# PCB-BI8-2x4_PCBAtest.net
KiCad netlist of a schematic drawn in EAGLE
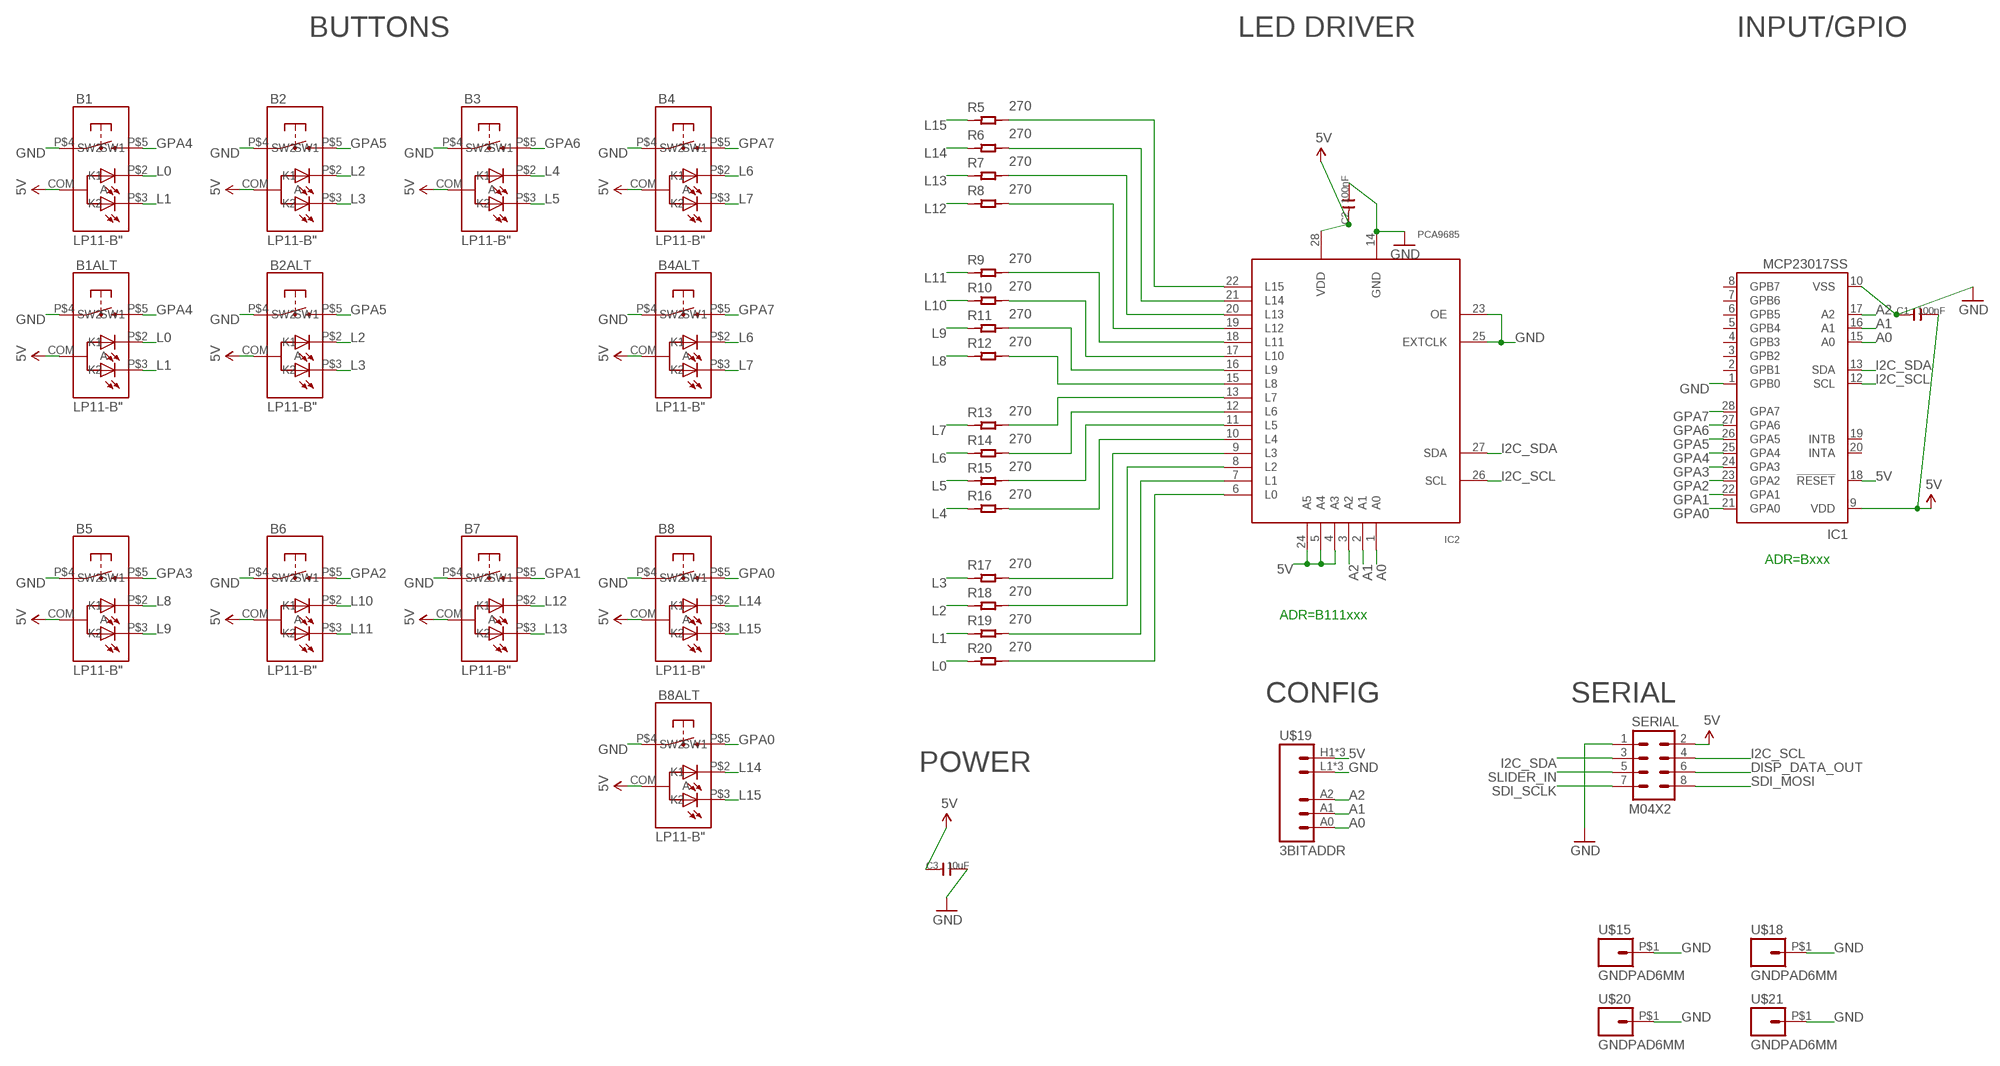
[diagram p0: schematic, sheet 1]

(export (version "E")
  (design (tool "Eeschema 10.0.6"))
  (components
    (comp (ref "B1")
      (value "LP11-B\"")
      (footprint "eagle-import:LP11")
      (libsource (lib "eagle-import") (part "LP11-B{dblquote}"))
    )
    (comp (ref "B1ALT")
      (value "LP11-B\"")
      (footprint "eagle-import:LP11")
      (libsource (lib "eagle-import") (part "LP11-B{dblquote}"))
    )
    (comp (ref "B2")
      (value "LP11-B\"")
      (footprint "eagle-import:LP11")
      (libsource (lib "eagle-import") (part "LP11-B{dblquote}"))
    )
    (comp (ref "B2ALT")
      (value "LP11-B\"")
      (footprint "eagle-import:LP11")
      (libsource (lib "eagle-import") (part "LP11-B{dblquote}"))
    )
    (comp (ref "B3")
      (value "LP11-B\"")
      (footprint "eagle-import:LP11")
      (libsource (lib "eagle-import") (part "LP11-B{dblquote}"))
    )
    (comp (ref "B4")
      (value "LP11-B\"")
      (footprint "eagle-import:LP11")
      (libsource (lib "eagle-import") (part "LP11-B{dblquote}"))
    )
    (comp (ref "B4ALT")
      (value "LP11-B\"")
      (footprint "eagle-import:LP11")
      (libsource (lib "eagle-import") (part "LP11-B{dblquote}"))
    )
    (comp (ref "B5")
      (value "LP11-B\"")
      (footprint "eagle-import:LP11")
      (libsource (lib "eagle-import") (part "LP11-B{dblquote}"))
    )
    (comp (ref "B6")
      (value "LP11-B\"")
      (footprint "eagle-import:LP11")
      (libsource (lib "eagle-import") (part "LP11-B{dblquote}"))
    )
    (comp (ref "B7")
      (value "LP11-B\"")
      (footprint "eagle-import:LP11")
      (libsource (lib "eagle-import") (part "LP11-B{dblquote}"))
    )
    (comp (ref "B8")
      (value "LP11-B\"")
      (footprint "eagle-import:LP11")
      (libsource (lib "eagle-import") (part "LP11-B{dblquote}"))
    )
    (comp (ref "B8ALT")
      (value "LP11-B\"")
      (footprint "eagle-import:LP11")
      (libsource (lib "eagle-import") (part "LP11-B{dblquote}"))
    )
    (comp (ref "C1")
      (value "100nF")
      (footprint "eagle-import:C0603")
      (libsource (lib "eagle-import") (part "C-0603"))
    )
    (comp (ref "C2")
      (value "100nF")
      (footprint "eagle-import:C0603")
      (libsource (lib "eagle-import") (part "C-0603"))
    )
    (comp (ref "C3")
      (value "10uF")
      (footprint "eagle-import:C0805")
      (libsource (lib "eagle-import") (part "C-0805"))
    )
    (comp (ref "IC1")
      (value "MCP23017SS")
      (footprint "eagle-import:SSOP28")
      (fields
        (field (name "MF") "MICROCHIP")
        (field (name "MPN") "MCP23017-E/SS")
        (field (name "MPN_1") "MCP23017-E/SS")
        (field (name "OC_FARNELL") "1467674")
        (field (name "OC_NEWARK") "31K2960")
      )
      (libsource (lib "eagle-import") (part "MCP23017SS"))
    )
    (comp (ref "IC2")
      (value "PCA9685")
      (footprint "eagle-import:TSSOP28")
      (libsource (lib "eagle-import") (part "PCA9685"))
    )
    (comp (ref "R5")
      (value "270")
      (footprint "eagle-import:R0603")
      (libsource (lib "eagle-import") (part "R-0603"))
    )
    (comp (ref "R6")
      (value "270")
      (footprint "eagle-import:R0603")
      (libsource (lib "eagle-import") (part "R-0603"))
    )
    (comp (ref "R7")
      (value "270")
      (footprint "eagle-import:R0603")
      (libsource (lib "eagle-import") (part "R-0603"))
    )
    (comp (ref "R8")
      (value "270")
      (footprint "eagle-import:R0603")
      (libsource (lib "eagle-import") (part "R-0603"))
    )
    (comp (ref "R9")
      (value "270")
      (footprint "eagle-import:R0603")
      (libsource (lib "eagle-import") (part "R-0603"))
    )
    (comp (ref "R10")
      (value "270")
      (footprint "eagle-import:R0603")
      (libsource (lib "eagle-import") (part "R-0603"))
    )
    (comp (ref "R11")
      (value "270")
      (footprint "eagle-import:R0603")
      (libsource (lib "eagle-import") (part "R-0603"))
    )
    (comp (ref "R12")
      (value "270")
      (footprint "eagle-import:R0603")
      (libsource (lib "eagle-import") (part "R-0603"))
    )
    (comp (ref "R13")
      (value "270")
      (footprint "eagle-import:R0603")
      (libsource (lib "eagle-import") (part "R-0603"))
    )
    (comp (ref "R14")
      (value "270")
      (footprint "eagle-import:R0603")
      (libsource (lib "eagle-import") (part "R-0603"))
    )
    (comp (ref "R15")
      (value "270")
      (footprint "eagle-import:R0603")
      (libsource (lib "eagle-import") (part "R-0603"))
    )
    (comp (ref "R16")
      (value "270")
      (footprint "eagle-import:R0603")
      (libsource (lib "eagle-import") (part "R-0603"))
    )
    (comp (ref "R17")
      (value "270")
      (footprint "eagle-import:R0603")
      (libsource (lib "eagle-import") (part "R-0603"))
    )
    (comp (ref "R18")
      (value "270")
      (footprint "eagle-import:R0603")
      (libsource (lib "eagle-import") (part "R-0603"))
    )
    (comp (ref "R19")
      (value "270")
      (footprint "eagle-import:R0603")
      (libsource (lib "eagle-import") (part "R-0603"))
    )
    (comp (ref "R20")
      (value "270")
      (footprint "eagle-import:R0603")
      (libsource (lib "eagle-import") (part "R-0603"))
    )
    (comp (ref "SERIAL")
      (value "M04X2")
      (footprint "eagle-import:2X4")
      (libsource (lib "eagle-import") (part "M04X2"))
    )
    (comp (ref "U$15")
      (value "GNDPAD6MM")
      (footprint "eagle-import:3.2MMPAD6MM")
      (libsource (lib "eagle-import") (part "GNDPAD6MM"))
    )
    (comp (ref "U$18")
      (value "GNDPAD6MM")
      (footprint "eagle-import:3.2MMPAD6MM")
      (libsource (lib "eagle-import") (part "GNDPAD6MM"))
    )
    (comp (ref "U$19")
      (value "3BITADDR")
      (footprint "eagle-import:3BITADDR")
      (libsource (lib "eagle-import") (part "3BITADDR"))
    )
    (comp (ref "U$20")
      (value "GNDPAD6MM")
      (footprint "eagle-import:3.2MMPAD6MM")
      (libsource (lib "eagle-import") (part "GNDPAD6MM"))
    )
    (comp (ref "U$21")
      (value "GNDPAD6MM")
      (footprint "eagle-import:3.2MMPAD6MM")
      (libsource (lib "eagle-import") (part "GNDPAD6MM"))
    )
  )
  (nets
    (net (code "1") (name "5V") (class "Default")
      (node (ref "B1") (pin "COM") (pinfunction "A_COM") (pintype "bidirectional"))
      (node (ref "B1ALT") (pin "COM") (pinfunction "A_COM") (pintype "bidirectional"))
      (node (ref "B2") (pin "COM") (pinfunction "A_COM") (pintype "bidirectional"))
      (node (ref "B2ALT") (pin "COM") (pinfunction "A_COM") (pintype "bidirectional"))
      (node (ref "B3") (pin "COM") (pinfunction "A_COM") (pintype "bidirectional"))
      (node (ref "B4") (pin "COM") (pinfunction "A_COM") (pintype "bidirectional"))
      (node (ref "B4ALT") (pin "COM") (pinfunction "A_COM") (pintype "bidirectional"))
      (node (ref "B5") (pin "COM") (pinfunction "A_COM") (pintype "bidirectional"))
      (node (ref "B6") (pin "COM") (pinfunction "A_COM") (pintype "bidirectional"))
      (node (ref "B7") (pin "COM") (pinfunction "A_COM") (pintype "bidirectional"))
      (node (ref "B8") (pin "COM") (pinfunction "A_COM") (pintype "bidirectional"))
      (node (ref "B8ALT") (pin "COM") (pinfunction "A_COM") (pintype "bidirectional"))
      (node (ref "C1") (pin "2") (pinfunction "2_2") (pintype "bidirectional"))
      (node (ref "C2") (pin "1") (pinfunction "1_1") (pintype "bidirectional"))
      (node (ref "C3") (pin "1") (pinfunction "1_1") (pintype "bidirectional"))
      (node (ref "IC1") (pin "18") (pinfunction "~{RESET}_18") (pintype "input"))
      (node (ref "IC1") (pin "9") (pinfunction "VDD_9") (pintype "power_in"))
      (node (ref "IC2") (pin "24") (pinfunction "A5_24") (pintype "input"))
      (node (ref "IC2") (pin "28") (pinfunction "VDD_28") (pintype "power_in"))
      (node (ref "IC2") (pin "4") (pinfunction "A3_4") (pintype "input"))
      (node (ref "IC2") (pin "5") (pinfunction "A4_5") (pintype "input"))
      (node (ref "SERIAL") (pin "2") (pinfunction "2_2") (pintype "passive"))
      (node (ref "U$19") (pin "H1") (pinfunction "VCC_H1") (pintype "passive"))
      (node (ref "U$19") (pin "H2") (pinfunction "VCC_H2") (pintype "passive"))
      (node (ref "U$19") (pin "H3") (pinfunction "VCC_H3") (pintype "passive"))
    )
    (net (code "2") (name "A0") (class "Default")
      (node (ref "IC1") (pin "15") (pinfunction "A0_15") (pintype "input"))
      (node (ref "IC2") (pin "1") (pinfunction "A0_1") (pintype "input"))
      (node (ref "U$19") (pin "A0") (pinfunction "A0_A0") (pintype "passive"))
    )
    (net (code "3") (name "A1") (class "Default")
      (node (ref "IC1") (pin "16") (pinfunction "A1_16") (pintype "input"))
      (node (ref "IC2") (pin "2") (pinfunction "A1_2") (pintype "input"))
      (node (ref "U$19") (pin "A1") (pinfunction "A1_A1") (pintype "passive"))
    )
    (net (code "4") (name "A2") (class "Default")
      (node (ref "IC1") (pin "17") (pinfunction "A2_17") (pintype "input"))
      (node (ref "IC2") (pin "3") (pinfunction "A2_3") (pintype "input"))
      (node (ref "U$19") (pin "A2") (pinfunction "A2_A2") (pintype "passive"))
    )
    (net (code "5") (name "DISP_DATA_OUT") (class "Default")
      (node (ref "SERIAL") (pin "6") (pinfunction "6_6") (pintype "passive"))
    )
    (net (code "6") (name "GND") (class "Default")
      (node (ref "B1") (pin "P$4") (pinfunction "SW1_P$4") (pintype "bidirectional"))
      (node (ref "B1ALT") (pin "P$4") (pinfunction "SW1_P$4") (pintype "bidirectional"))
      (node (ref "B2") (pin "P$4") (pinfunction "SW1_P$4") (pintype "bidirectional"))
      (node (ref "B2ALT") (pin "P$4") (pinfunction "SW1_P$4") (pintype "bidirectional"))
      (node (ref "B3") (pin "P$4") (pinfunction "SW1_P$4") (pintype "bidirectional"))
      (node (ref "B4") (pin "P$4") (pinfunction "SW1_P$4") (pintype "bidirectional"))
      (node (ref "B4ALT") (pin "P$4") (pinfunction "SW1_P$4") (pintype "bidirectional"))
      (node (ref "B5") (pin "P$4") (pinfunction "SW1_P$4") (pintype "bidirectional"))
      (node (ref "B6") (pin "P$4") (pinfunction "SW1_P$4") (pintype "bidirectional"))
      (node (ref "B7") (pin "P$4") (pinfunction "SW1_P$4") (pintype "bidirectional"))
      (node (ref "B8") (pin "P$4") (pinfunction "SW1_P$4") (pintype "bidirectional"))
      (node (ref "B8ALT") (pin "P$4") (pinfunction "SW1_P$4") (pintype "bidirectional"))
      (node (ref "C1") (pin "1") (pinfunction "1_1") (pintype "bidirectional"))
      (node (ref "C2") (pin "2") (pinfunction "2_2") (pintype "bidirectional"))
      (node (ref "C3") (pin "2") (pinfunction "2_2") (pintype "bidirectional"))
      (node (ref "IC1") (pin "1") (pinfunction "GPB0_1") (pintype "bidirectional"))
      (node (ref "IC1") (pin "10") (pinfunction "VSS_10") (pintype "power_in"))
      (node (ref "IC2") (pin "14") (pinfunction "GND_14") (pintype "power_in"))
      (node (ref "IC2") (pin "23") (pinfunction "OE_23") (pintype "input"))
      (node (ref "IC2") (pin "25") (pinfunction "EXTCLK_25") (pintype "input"))
      (node (ref "SERIAL") (pin "1") (pinfunction "1_1") (pintype "passive"))
      (node (ref "U$15") (pin "P$1") (pinfunction "1_P$1") (pintype "passive"))
      (node (ref "U$18") (pin "P$1") (pinfunction "1_P$1") (pintype "passive"))
      (node (ref "U$19") (pin "L1") (pinfunction "GND_L1") (pintype "passive"))
      (node (ref "U$19") (pin "L2") (pinfunction "GND_L2") (pintype "passive"))
      (node (ref "U$19") (pin "L3") (pinfunction "GND_L3") (pintype "passive"))
      (node (ref "U$20") (pin "P$1") (pinfunction "1_P$1") (pintype "passive"))
      (node (ref "U$21") (pin "P$1") (pinfunction "1_P$1") (pintype "passive"))
    )
    (net (code "7") (name "GPA0") (class "Default")
      (node (ref "B8") (pin "P$5") (pinfunction "SW2_P$5") (pintype "bidirectional"))
      (node (ref "B8ALT") (pin "P$5") (pinfunction "SW2_P$5") (pintype "bidirectional"))
      (node (ref "IC1") (pin "21") (pinfunction "GPA0_21") (pintype "bidirectional"))
    )
    (net (code "8") (name "GPA1") (class "Default")
      (node (ref "B7") (pin "P$5") (pinfunction "SW2_P$5") (pintype "bidirectional"))
      (node (ref "IC1") (pin "22") (pinfunction "GPA1_22") (pintype "bidirectional"))
    )
    (net (code "9") (name "GPA2") (class "Default")
      (node (ref "B6") (pin "P$5") (pinfunction "SW2_P$5") (pintype "bidirectional"))
      (node (ref "IC1") (pin "23") (pinfunction "GPA2_23") (pintype "bidirectional"))
    )
    (net (code "10") (name "GPA3") (class "Default")
      (node (ref "B5") (pin "P$5") (pinfunction "SW2_P$5") (pintype "bidirectional"))
      (node (ref "IC1") (pin "24") (pinfunction "GPA3_24") (pintype "bidirectional"))
    )
    (net (code "11") (name "GPA4") (class "Default")
      (node (ref "B1") (pin "P$5") (pinfunction "SW2_P$5") (pintype "bidirectional"))
      (node (ref "B1ALT") (pin "P$5") (pinfunction "SW2_P$5") (pintype "bidirectional"))
      (node (ref "IC1") (pin "25") (pinfunction "GPA4_25") (pintype "bidirectional"))
    )
    (net (code "12") (name "GPA5") (class "Default")
      (node (ref "B2") (pin "P$5") (pinfunction "SW2_P$5") (pintype "bidirectional"))
      (node (ref "B2ALT") (pin "P$5") (pinfunction "SW2_P$5") (pintype "bidirectional"))
      (node (ref "IC1") (pin "26") (pinfunction "GPA5_26") (pintype "bidirectional"))
    )
    (net (code "13") (name "GPA6") (class "Default")
      (node (ref "B3") (pin "P$5") (pinfunction "SW2_P$5") (pintype "bidirectional"))
      (node (ref "IC1") (pin "27") (pinfunction "GPA6_27") (pintype "bidirectional"))
    )
    (net (code "14") (name "GPA7") (class "Default")
      (node (ref "B4") (pin "P$5") (pinfunction "SW2_P$5") (pintype "bidirectional"))
      (node (ref "B4ALT") (pin "P$5") (pinfunction "SW2_P$5") (pintype "bidirectional"))
      (node (ref "IC1") (pin "28") (pinfunction "GPA7_28") (pintype "bidirectional"))
    )
    (net (code "15") (name "I2C_SCL") (class "Default")
      (node (ref "IC1") (pin "12") (pinfunction "SCL_12") (pintype "input"))
      (node (ref "IC2") (pin "26") (pinfunction "SCL_26") (pintype "input"))
      (node (ref "SERIAL") (pin "4") (pinfunction "4_4") (pintype "passive"))
    )
    (net (code "16") (name "I2C_SDA") (class "Default")
      (node (ref "IC1") (pin "13") (pinfunction "SDA_13") (pintype "bidirectional"))
      (node (ref "IC2") (pin "27") (pinfunction "SDA_27") (pintype "input"))
      (node (ref "SERIAL") (pin "3") (pinfunction "3_3") (pintype "passive"))
    )
    (net (code "17") (name "L0") (class "Default")
      (node (ref "B1") (pin "P$2") (pinfunction "K1_P$2") (pintype "bidirectional"))
      (node (ref "B1ALT") (pin "P$2") (pinfunction "K1_P$2") (pintype "bidirectional"))
      (node (ref "R20") (pin "1") (pinfunction "1_1") (pintype "bidirectional"))
    )
    (net (code "18") (name "L1") (class "Default")
      (node (ref "B1") (pin "P$3") (pinfunction "K2_P$3") (pintype "bidirectional"))
      (node (ref "B1ALT") (pin "P$3") (pinfunction "K2_P$3") (pintype "bidirectional"))
      (node (ref "R19") (pin "1") (pinfunction "1_1") (pintype "bidirectional"))
    )
    (net (code "19") (name "L2") (class "Default")
      (node (ref "B2") (pin "P$2") (pinfunction "K1_P$2") (pintype "bidirectional"))
      (node (ref "B2ALT") (pin "P$2") (pinfunction "K1_P$2") (pintype "bidirectional"))
      (node (ref "R18") (pin "1") (pinfunction "1_1") (pintype "bidirectional"))
    )
    (net (code "20") (name "L3") (class "Default")
      (node (ref "B2") (pin "P$3") (pinfunction "K2_P$3") (pintype "bidirectional"))
      (node (ref "B2ALT") (pin "P$3") (pinfunction "K2_P$3") (pintype "bidirectional"))
      (node (ref "R17") (pin "1") (pinfunction "1_1") (pintype "bidirectional"))
    )
    (net (code "21") (name "L4") (class "Default")
      (node (ref "B3") (pin "P$2") (pinfunction "K1_P$2") (pintype "bidirectional"))
      (node (ref "R16") (pin "1") (pinfunction "1_1") (pintype "bidirectional"))
    )
    (net (code "22") (name "L5") (class "Default")
      (node (ref "B3") (pin "P$3") (pinfunction "K2_P$3") (pintype "bidirectional"))
      (node (ref "R15") (pin "1") (pinfunction "1_1") (pintype "bidirectional"))
    )
    (net (code "23") (name "L6") (class "Default")
      (node (ref "B4") (pin "P$2") (pinfunction "K1_P$2") (pintype "bidirectional"))
      (node (ref "B4ALT") (pin "P$2") (pinfunction "K1_P$2") (pintype "bidirectional"))
      (node (ref "R14") (pin "1") (pinfunction "1_1") (pintype "bidirectional"))
    )
    (net (code "24") (name "L7") (class "Default")
      (node (ref "B4") (pin "P$3") (pinfunction "K2_P$3") (pintype "bidirectional"))
      (node (ref "B4ALT") (pin "P$3") (pinfunction "K2_P$3") (pintype "bidirectional"))
      (node (ref "R13") (pin "1") (pinfunction "1_1") (pintype "bidirectional"))
    )
    (net (code "25") (name "L8") (class "Default")
      (node (ref "B5") (pin "P$2") (pinfunction "K1_P$2") (pintype "bidirectional"))
      (node (ref "R12") (pin "1") (pinfunction "1_1") (pintype "bidirectional"))
    )
    (net (code "26") (name "L9") (class "Default")
      (node (ref "B5") (pin "P$3") (pinfunction "K2_P$3") (pintype "bidirectional"))
      (node (ref "R11") (pin "1") (pinfunction "1_1") (pintype "bidirectional"))
    )
    (net (code "27") (name "L10") (class "Default")
      (node (ref "B6") (pin "P$2") (pinfunction "K1_P$2") (pintype "bidirectional"))
      (node (ref "R10") (pin "1") (pinfunction "1_1") (pintype "bidirectional"))
    )
    (net (code "28") (name "L11") (class "Default")
      (node (ref "B6") (pin "P$3") (pinfunction "K2_P$3") (pintype "bidirectional"))
      (node (ref "R9") (pin "1") (pinfunction "1_1") (pintype "bidirectional"))
    )
    (net (code "29") (name "L12") (class "Default")
      (node (ref "B7") (pin "P$2") (pinfunction "K1_P$2") (pintype "bidirectional"))
      (node (ref "R8") (pin "1") (pinfunction "1_1") (pintype "bidirectional"))
    )
    (net (code "30") (name "L13") (class "Default")
      (node (ref "B7") (pin "P$3") (pinfunction "K2_P$3") (pintype "bidirectional"))
      (node (ref "R7") (pin "1") (pinfunction "1_1") (pintype "bidirectional"))
    )
    (net (code "31") (name "L14") (class "Default")
      (node (ref "B8") (pin "P$2") (pinfunction "K1_P$2") (pintype "bidirectional"))
      (node (ref "B8ALT") (pin "P$2") (pinfunction "K1_P$2") (pintype "bidirectional"))
      (node (ref "R6") (pin "1") (pinfunction "1_1") (pintype "bidirectional"))
    )
    (net (code "32") (name "L15") (class "Default")
      (node (ref "B8") (pin "P$3") (pinfunction "K2_P$3") (pintype "bidirectional"))
      (node (ref "B8ALT") (pin "P$3") (pinfunction "K2_P$3") (pintype "bidirectional"))
      (node (ref "R5") (pin "1") (pinfunction "1_1") (pintype "bidirectional"))
    )
    (net (code "33") (name "Net-(IC2-L0)") (class "Default")
      (node (ref "IC2") (pin "6") (pinfunction "L0_6") (pintype "output"))
      (node (ref "R20") (pin "2") (pinfunction "2_2") (pintype "bidirectional"))
    )
    (net (code "34") (name "Net-(IC2-L1)") (class "Default")
      (node (ref "IC2") (pin "7") (pinfunction "L1_7") (pintype "output"))
      (node (ref "R19") (pin "2") (pinfunction "2_2") (pintype "bidirectional"))
    )
    (net (code "35") (name "Net-(IC2-L2)") (class "Default")
      (node (ref "IC2") (pin "8") (pinfunction "L2_8") (pintype "output"))
      (node (ref "R18") (pin "2") (pinfunction "2_2") (pintype "bidirectional"))
    )
    (net (code "36") (name "Net-(IC2-L3)") (class "Default")
      (node (ref "IC2") (pin "9") (pinfunction "L3_9") (pintype "output"))
      (node (ref "R17") (pin "2") (pinfunction "2_2") (pintype "bidirectional"))
    )
    (net (code "37") (name "Net-(IC2-L4)") (class "Default")
      (node (ref "IC2") (pin "10") (pinfunction "L4_10") (pintype "output"))
      (node (ref "R16") (pin "2") (pinfunction "2_2") (pintype "bidirectional"))
    )
    (net (code "38") (name "Net-(IC2-L5)") (class "Default")
      (node (ref "IC2") (pin "11") (pinfunction "L5_11") (pintype "output"))
      (node (ref "R15") (pin "2") (pinfunction "2_2") (pintype "bidirectional"))
    )
    (net (code "39") (name "Net-(IC2-L6)") (class "Default")
      (node (ref "IC2") (pin "12") (pinfunction "L6_12") (pintype "output"))
      (node (ref "R14") (pin "2") (pinfunction "2_2") (pintype "bidirectional"))
    )
    (net (code "40") (name "Net-(IC2-L7)") (class "Default")
      (node (ref "IC2") (pin "13") (pinfunction "L7_13") (pintype "output"))
      (node (ref "R13") (pin "2") (pinfunction "2_2") (pintype "bidirectional"))
    )
    (net (code "41") (name "Net-(IC2-L8)") (class "Default")
      (node (ref "IC2") (pin "15") (pinfunction "L8_15") (pintype "output"))
      (node (ref "R12") (pin "2") (pinfunction "2_2") (pintype "bidirectional"))
    )
    (net (code "42") (name "Net-(IC2-L9)") (class "Default")
      (node (ref "IC2") (pin "16") (pinfunction "L9_16") (pintype "output"))
      (node (ref "R11") (pin "2") (pinfunction "2_2") (pintype "bidirectional"))
    )
    (net (code "43") (name "Net-(IC2-L10)") (class "Default")
      (node (ref "IC2") (pin "17") (pinfunction "L10_17") (pintype "output"))
      (node (ref "R10") (pin "2") (pinfunction "2_2") (pintype "bidirectional"))
    )
    (net (code "44") (name "Net-(IC2-L11)") (class "Default")
      (node (ref "IC2") (pin "18") (pinfunction "L11_18") (pintype "output"))
      (node (ref "R9") (pin "2") (pinfunction "2_2") (pintype "bidirectional"))
    )
    (net (code "45") (name "Net-(IC2-L12)") (class "Default")
      (node (ref "IC2") (pin "19") (pinfunction "L12_19") (pintype "output"))
      (node (ref "R8") (pin "2") (pinfunction "2_2") (pintype "bidirectional"))
    )
    (net (code "46") (name "Net-(IC2-L13)") (class "Default")
      (node (ref "IC2") (pin "20") (pinfunction "L13_20") (pintype "output"))
      (node (ref "R7") (pin "2") (pinfunction "2_2") (pintype "bidirectional"))
    )
    (net (code "47") (name "Net-(IC2-L14)") (class "Default")
      (node (ref "IC2") (pin "21") (pinfunction "L14_21") (pintype "output"))
      (node (ref "R6") (pin "2") (pinfunction "2_2") (pintype "bidirectional"))
    )
    (net (code "48") (name "Net-(IC2-L15)") (class "Default")
      (node (ref "IC2") (pin "22") (pinfunction "L15_22") (pintype "output"))
      (node (ref "R5") (pin "2") (pinfunction "2_2") (pintype "bidirectional"))
    )
    (net (code "49") (name "SDI_MOSI") (class "Default")
      (node (ref "SERIAL") (pin "8") (pinfunction "8_8") (pintype "passive"))
    )
    (net (code "50") (name "SDI_SCLK") (class "Default")
      (node (ref "SERIAL") (pin "7") (pinfunction "7_7") (pintype "passive"))
    )
    (net (code "51") (name "SLIDER_IN") (class "Default")
      (node (ref "SERIAL") (pin "5") (pinfunction "5_5") (pintype "passive"))
    )
    (net (code "52") (name "unconnected-(IC1-GPB1-Pad2)") (class "Default")
      (node (ref "IC1") (pin "2") (pinfunction "GPB1_2") (pintype "bidirectional"))
    )
    (net (code "53") (name "unconnected-(IC1-GPB2-Pad3)") (class "Default")
      (node (ref "IC1") (pin "3") (pinfunction "GPB2_3") (pintype "bidirectional"))
    )
    (net (code "54") (name "unconnected-(IC1-GPB3-Pad4)") (class "Default")
      (node (ref "IC1") (pin "4") (pinfunction "GPB3_4") (pintype "bidirectional"))
    )
    (net (code "55") (name "unconnected-(IC1-GPB4-Pad5)") (class "Default")
      (node (ref "IC1") (pin "5") (pinfunction "GPB4_5") (pintype "bidirectional"))
    )
    (net (code "56") (name "unconnected-(IC1-GPB5-Pad6)") (class "Default")
      (node (ref "IC1") (pin "6") (pinfunction "GPB5_6") (pintype "bidirectional"))
    )
    (net (code "57") (name "unconnected-(IC1-GPB6-Pad7)") (class "Default")
      (node (ref "IC1") (pin "7") (pinfunction "GPB6_7") (pintype "bidirectional"))
    )
    (net (code "58") (name "unconnected-(IC1-GPB7-Pad8)") (class "Default")
      (node (ref "IC1") (pin "8") (pinfunction "GPB7_8") (pintype "bidirectional"))
    )
    (net (code "59") (name "unconnected-(IC1-INTA-Pad20)") (class "Default")
      (node (ref "IC1") (pin "20") (pinfunction "INTA_20") (pintype "output"))
    )
    (net (code "60") (name "unconnected-(IC1-INTB-Pad19)") (class "Default")
      (node (ref "IC1") (pin "19") (pinfunction "INTB_19") (pintype "output"))
    )
  )
)
